# fanctrl.net
KiCad netlist of a schematic drawn in EAGLE
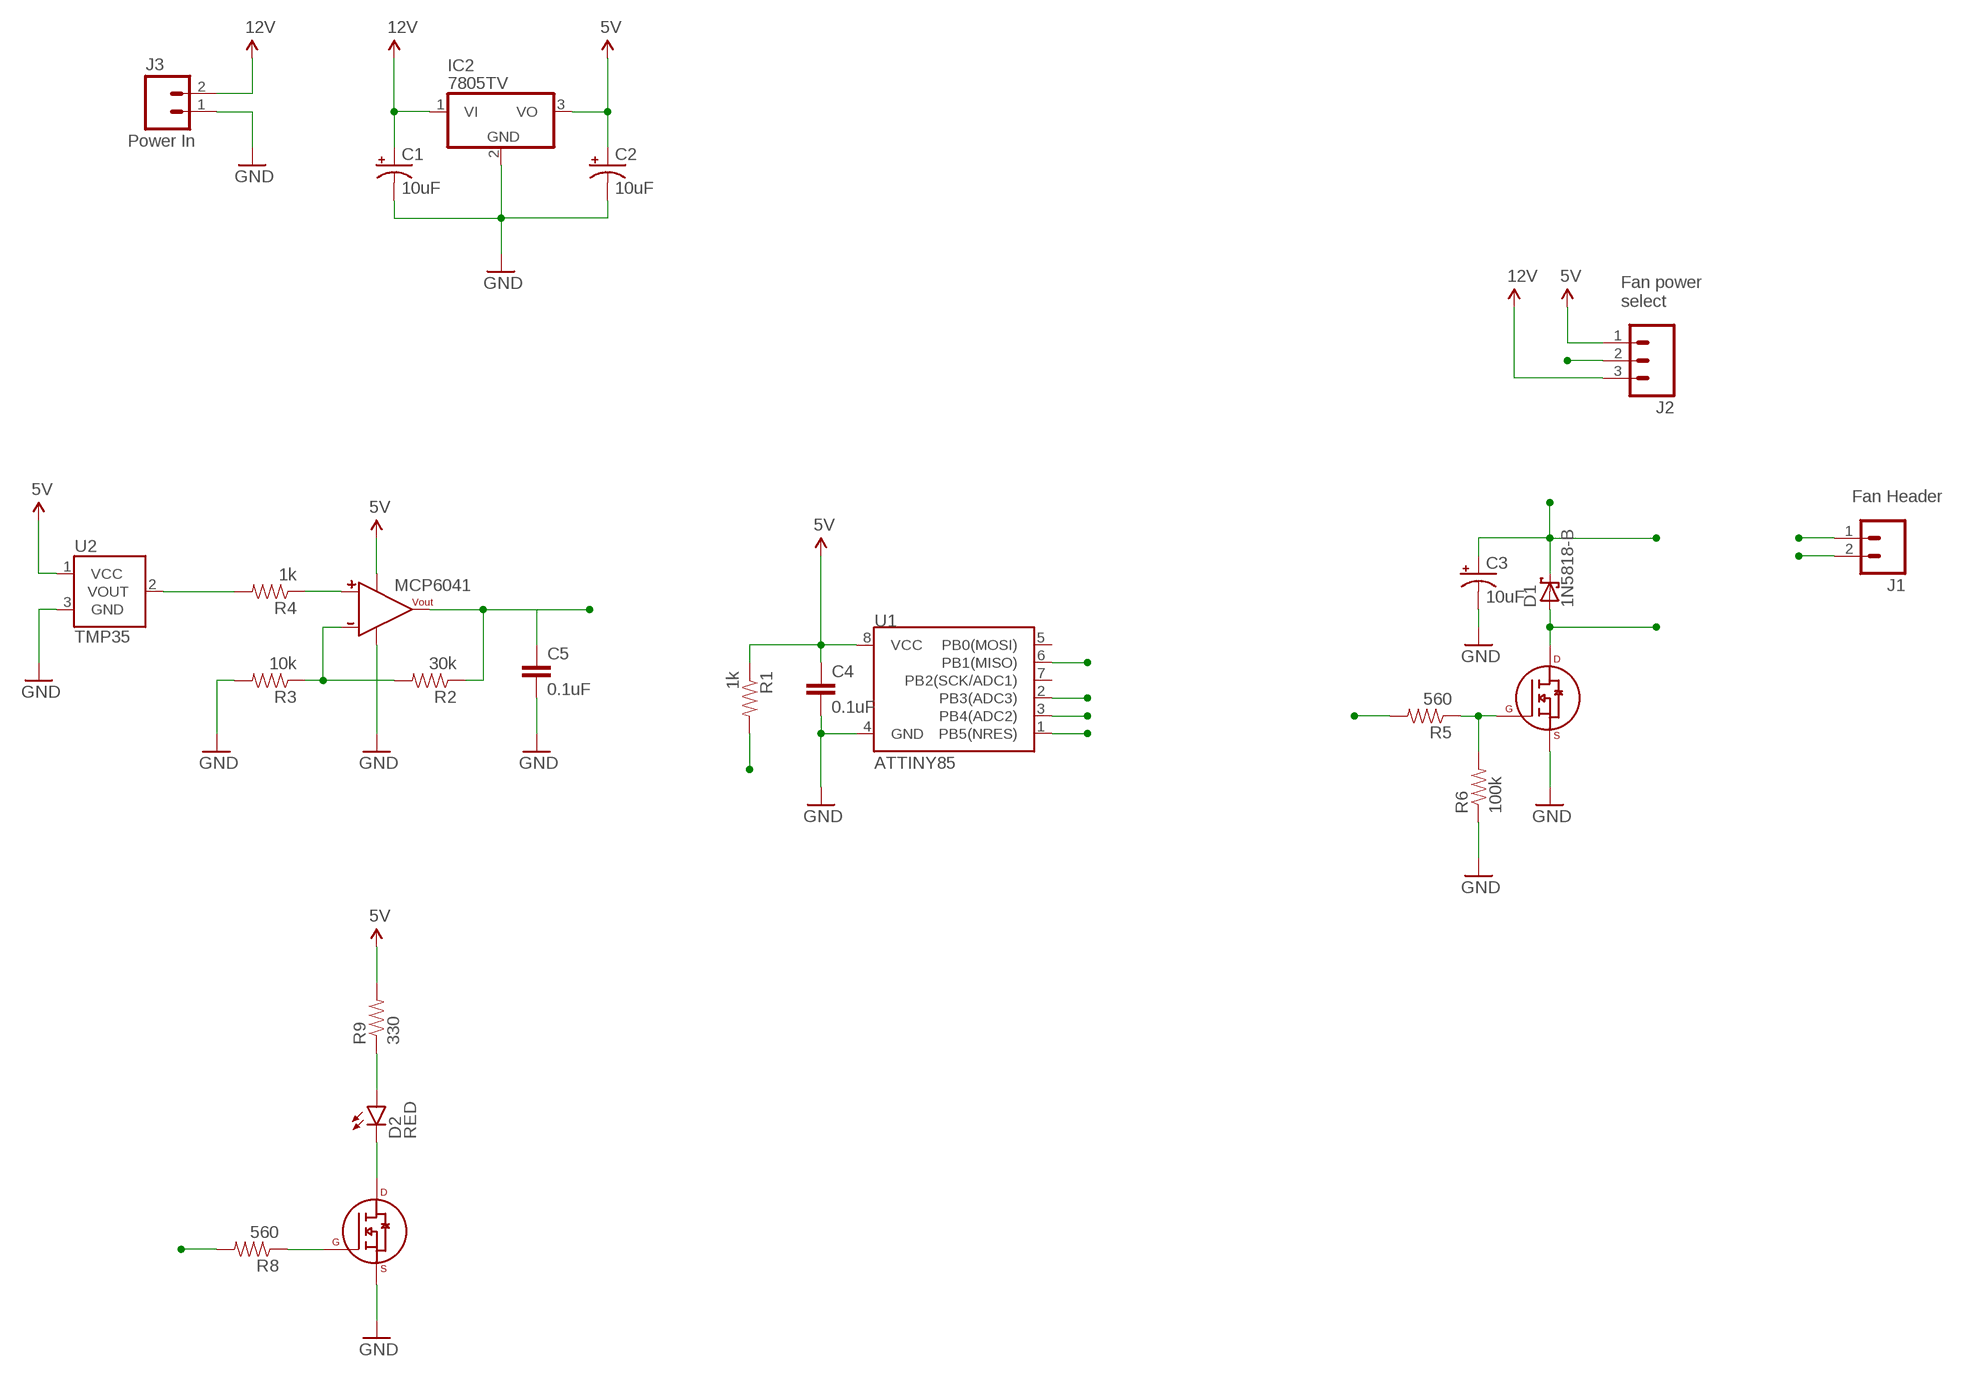
[diagram p0: schematic, sheet 1]

(export (version "E")
  (design (tool "Eeschema 10.0.6"))
  (components
    (comp (ref "C1")
      (value "10uF")
      (footprint "eagle-import:CPOL-RADIAL-10UF-25V")
      (libsource (lib "eagle-import") (part "10UF-25V-20%(PTH)"))
    )
    (comp (ref "C2")
      (value "10uF")
      (footprint "eagle-import:CPOL-RADIAL-10UF-25V")
      (libsource (lib "eagle-import") (part "10UF-25V-20%(PTH)"))
    )
    (comp (ref "C3")
      (value "10uF")
      (footprint "eagle-import:CPOL-RADIAL-10UF-25V")
      (libsource (lib "eagle-import") (part "10UF-25V-20%(PTH)"))
    )
    (comp (ref "C4")
      (value "0.1uF")
      (footprint "eagle-import:CAP-PTH-SMALLEZ")
      (libsource (lib "eagle-import") (part "CAPEZ"))
    )
    (comp (ref "C5")
      (value "0.1uF")
      (footprint "eagle-import:CAP-PTH-SMALLEZ")
      (libsource (lib "eagle-import") (part "CAPEZ"))
    )
    (comp (ref "D1")
      (value "1N5818-B")
      (footprint "eagle-import:DO41-7.6")
      (libsource (lib "eagle-import") (part "1N5818-B"))
    )
    (comp (ref "D2")
      (value "RED")
      (footprint "eagle-import:LED5MM")
      (libsource (lib "eagle-import") (part "LED5MM"))
    )
    (comp (ref "IC2")
      (value "7805TV")
      (footprint "eagle-import:TO220V")
      (libsource (lib "eagle-import") (part "78TV05"))
    )
    (comp (ref "J1")
      (value "M02JST-PTH-VERT")
      (footprint "eagle-import:JST-2-PTH-VERT")
      (libsource (lib "eagle-import") (part "M02JST-PTH-VERT"))
    )
    (comp (ref "J2")
      (value "M03PTH")
      (footprint "eagle-import:1X03")
      (libsource (lib "eagle-import") (part "M03PTH"))
    )
    (comp (ref "J3")
      (value "M02PTH")
      (footprint "eagle-import:1X02")
      (libsource (lib "eagle-import") (part "M02PTH"))
    )
    (comp (ref "MCP6041")
      (value "MCP6041DIP")
      (footprint "eagle-import:PDIP-8")
      (libsource (lib "eagle-import") (part "MCP6041DIP"))
    )
    (comp (ref "R1")
      (value "1k")
      (footprint "eagle-import:AXIAL-0.1")
      (libsource (lib "eagle-import") (part "RESISTORPTH-1/4W-VERT"))
    )
    (comp (ref "R2")
      (value "30k")
      (footprint "eagle-import:AXIAL-0.1")
      (libsource (lib "eagle-import") (part "RESISTORPTH-1/4W-VERT"))
    )
    (comp (ref "R3")
      (value "10k")
      (footprint "eagle-import:AXIAL-0.1")
      (libsource (lib "eagle-import") (part "RESISTORPTH-1/4W-VERT"))
    )
    (comp (ref "R4")
      (value "1k")
      (footprint "eagle-import:AXIAL-0.1")
      (libsource (lib "eagle-import") (part "RESISTORPTH-1/4W-VERT"))
    )
    (comp (ref "R5")
      (value "560")
      (footprint "eagle-import:AXIAL-0.1")
      (libsource (lib "eagle-import") (part "RESISTORPTH-1/4W-VERT"))
    )
    (comp (ref "R6")
      (value "100k")
      (footprint "eagle-import:AXIAL-0.1")
      (libsource (lib "eagle-import") (part "RESISTORPTH-1/4W-VERT"))
    )
    (comp (ref "R8")
      (value "560")
      (footprint "eagle-import:AXIAL-0.1")
      (libsource (lib "eagle-import") (part "RESISTORPTH-1/4W-VERT"))
    )
    (comp (ref "R9")
      (value "330")
      (footprint "eagle-import:AXIAL-0.1")
      (libsource (lib "eagle-import") (part "RESISTORPTH-1/4W-VERT"))
    )
    (comp (ref "U$1")
      (value "2N7000")
      (footprint "eagle-import:TO-92")
      (libsource (lib "eagle-import") (part "2N7000-2TO-92"))
    )
    (comp (ref "U$2")
      (value "2N7000")
      (footprint "eagle-import:TO-92")
      (libsource (lib "eagle-import") (part "2N7000-2TO-92"))
    )
    (comp (ref "U1")
      (value "ATTINY85")
      (footprint "eagle-import:DIP08")
      (libsource (lib "eagle-import") (part "ATTINY45TINY45-20-DIP"))
    )
    (comp (ref "U2")
      (value "TMP35")
      (footprint "eagle-import:TO-92")
      (libsource (lib "eagle-import") (part "TMP36GT9"))
    )
  )
  (nets
    (net (code "1") (name "/FAN_POWER") (class "Default")
      (node (ref "C3") (pin "1") (pinfunction "+_1") (pintype "passive"))
      (node (ref "D1") (pin "C") (pinfunction "C_C") (pintype "passive"))
      (node (ref "J1") (pin "1") (pinfunction "1_1") (pintype "passive"))
      (node (ref "J2") (pin "2") (pinfunction "2_2") (pintype "passive"))
    )
    (net (code "2") (name "/LED") (class "Default")
      (node (ref "R8") (pin "P$2") (pinfunction "2_P$2") (pintype "passive"))
      (node (ref "U1") (pin "3") (pinfunction "PB4(ADC2)_3") (pintype "bidirectional"))
    )
    (net (code "3") (name "/MOTOR-") (class "Default")
      (node (ref "D1") (pin "A") (pinfunction "A_A") (pintype "passive"))
      (node (ref "J1") (pin "2") (pinfunction "2_2") (pintype "passive"))
      (node (ref "U$1") (pin "1") (pinfunction "D_1") (pintype "bidirectional"))
    )
    (net (code "4") (name "/PWM") (class "Default")
      (node (ref "R5") (pin "P$2") (pinfunction "2_P$2") (pintype "passive"))
      (node (ref "U1") (pin "6") (pinfunction "PB1(MISO)_6") (pintype "bidirectional"))
    )
    (net (code "5") (name "/SENSOR") (class "Default")
      (node (ref "C5") (pin "1") (pinfunction "1_1") (pintype "passive"))
      (node (ref "MCP6041") (pin "6") (pinfunction "VOUT_6") (pintype "output"))
      (node (ref "R2") (pin "P$1") (pinfunction "1_P$1") (pintype "passive"))
      (node (ref "U1") (pin "2") (pinfunction "PB3(ADC3)_2") (pintype "bidirectional"))
    )
    (net (code "6") (name "/{slash}RESET") (class "Default")
      (node (ref "R1") (pin "P$2") (pinfunction "2_P$2") (pintype "passive"))
      (node (ref "U1") (pin "1") (pinfunction "PB5(NRES)_1") (pintype "bidirectional"))
    )
    (net (code "7") (name "5V") (class "Default")
      (node (ref "C2") (pin "1") (pinfunction "+_1") (pintype "passive"))
      (node (ref "C4") (pin "1") (pinfunction "1_1") (pintype "passive"))
      (node (ref "IC2") (pin "3") (pinfunction "VO_3") (pintype "passive"))
      (node (ref "J2") (pin "1") (pinfunction "1_1") (pintype "passive"))
      (node (ref "MCP6041") (pin "7") (pinfunction "VDD_7") (pintype "power_in"))
      (node (ref "R1") (pin "P$1") (pinfunction "1_P$1") (pintype "passive"))
      (node (ref "R9") (pin "P$2") (pinfunction "2_P$2") (pintype "passive"))
      (node (ref "U1") (pin "8") (pinfunction "VCC_8") (pintype "bidirectional"))
      (node (ref "U2") (pin "1") (pinfunction "VCC_1") (pintype "bidirectional"))
    )
    (net (code "8") (name "12V") (class "Default")
      (node (ref "C1") (pin "1") (pinfunction "+_1") (pintype "passive"))
      (node (ref "IC2") (pin "1") (pinfunction "VI_1") (pintype "input"))
      (node (ref "J2") (pin "3") (pinfunction "3_3") (pintype "passive"))
      (node (ref "J3") (pin "2") (pinfunction "2_2") (pintype "passive"))
    )
    (net (code "9") (name "GND") (class "Default")
      (node (ref "C1") (pin "2") (pinfunction "-_2") (pintype "passive"))
      (node (ref "C2") (pin "2") (pinfunction "-_2") (pintype "passive"))
      (node (ref "C3") (pin "2") (pinfunction "-_2") (pintype "passive"))
      (node (ref "C4") (pin "2") (pinfunction "2_2") (pintype "passive"))
      (node (ref "C5") (pin "2") (pinfunction "2_2") (pintype "passive"))
      (node (ref "IC2") (pin "2") (pinfunction "GND_2") (pintype "passive"))
      (node (ref "J3") (pin "1") (pinfunction "1_1") (pintype "passive"))
      (node (ref "MCP6041") (pin "4") (pinfunction "VSS_4") (pintype "power_in"))
      (node (ref "R3") (pin "P$2") (pinfunction "2_P$2") (pintype "passive"))
      (node (ref "R6") (pin "P$1") (pinfunction "1_P$1") (pintype "passive"))
      (node (ref "U$1") (pin "3") (pinfunction "S_3") (pintype "bidirectional"))
      (node (ref "U$2") (pin "3") (pinfunction "S_3") (pintype "bidirectional"))
      (node (ref "U1") (pin "4") (pinfunction "GND_4") (pintype "bidirectional"))
      (node (ref "U2") (pin "3") (pinfunction "GND_3") (pintype "bidirectional"))
    )
    (net (code "10") (name "Net-(D2-C)") (class "Default")
      (node (ref "D2") (pin "K") (pinfunction "C_K") (pintype "passive"))
      (node (ref "U$2") (pin "1") (pinfunction "D_1") (pintype "bidirectional"))
    )
    (net (code "11") (name "Net-(MCP6041-+)") (class "Default")
      (node (ref "MCP6041") (pin "3") (pinfunction "+_3") (pintype "input"))
      (node (ref "R4") (pin "P$1") (pinfunction "1_P$1") (pintype "passive"))
    )
    (net (code "12") (name "Net-(MCP6041--)") (class "Default")
      (node (ref "MCP6041") (pin "2") (pinfunction "-_2") (pintype "input"))
      (node (ref "R2") (pin "P$2") (pinfunction "2_P$2") (pintype "passive"))
      (node (ref "R3") (pin "P$1") (pinfunction "1_P$1") (pintype "passive"))
    )
    (net (code "13") (name "Net-(R4-2)") (class "Default")
      (node (ref "R4") (pin "P$2") (pinfunction "2_P$2") (pintype "passive"))
      (node (ref "U2") (pin "2") (pinfunction "VOUT_2") (pintype "bidirectional"))
    )
    (net (code "14") (name "Net-(R5-1)") (class "Default")
      (node (ref "R5") (pin "P$1") (pinfunction "1_P$1") (pintype "passive"))
      (node (ref "R6") (pin "P$2") (pinfunction "2_P$2") (pintype "passive"))
      (node (ref "U$1") (pin "2") (pinfunction "G_2") (pintype "bidirectional"))
    )
    (net (code "15") (name "Net-(R8-1)") (class "Default")
      (node (ref "R8") (pin "P$1") (pinfunction "1_P$1") (pintype "passive"))
      (node (ref "U$2") (pin "2") (pinfunction "G_2") (pintype "bidirectional"))
    )
    (net (code "16") (name "Net-(R9-1)") (class "Default")
      (node (ref "D2") (pin "A") (pinfunction "A_A") (pintype "passive"))
      (node (ref "R9") (pin "P$1") (pinfunction "1_P$1") (pintype "passive"))
    )
    (net (code "17") (name "unconnected-(U1-PB0(MOSI)-Pad5)") (class "Default")
      (node (ref "U1") (pin "5") (pinfunction "PB0(MOSI)_5") (pintype "bidirectional"))
    )
    (net (code "18") (name "unconnected-(U1-PB2(SCK{slash}ADC1)-Pad7)") (class "Default")
      (node (ref "U1") (pin "7") (pinfunction "PB2(SCK/ADC1)_7") (pintype "bidirectional"))
    )
  )
)
